# afraid_of_the_dark.net
KiCad netlist of a schematic drawn in EAGLE
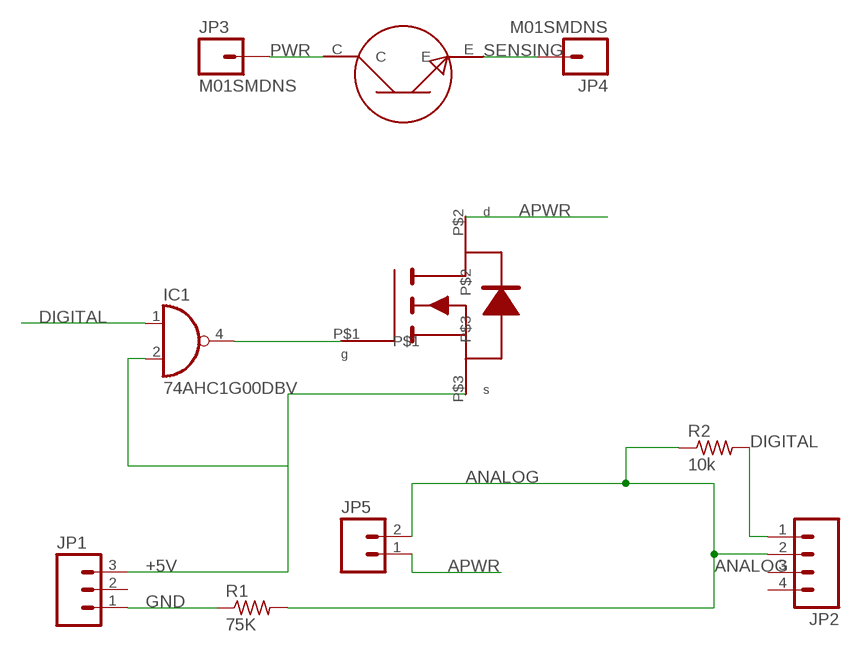
[diagram p0: schematic, sheet 1]

(export (version "E")
  (design (tool "Eeschema 10.0.6"))
  (components
    (comp (ref "IC1")
      (value "74AHC1G00DBV")
      (footprint "eagle-import:SOT23-5")
      (libsource (lib "eagle-import") (part "741G00DBVAHC"))
    )
    (comp (ref "JP1")
      (value "M03PTH")
      (footprint "eagle-import:1X03")
      (libsource (lib "eagle-import") (part "M03PTH"))
    )
    (comp (ref "JP2")
      (value "M04PTH")
      (footprint "eagle-import:1X04")
      (libsource (lib "eagle-import") (part "M04PTH"))
    )
    (comp (ref "JP3")
      (value "M01SMDNS")
      (footprint "eagle-import:1X01NS")
      (libsource (lib "eagle-import") (part "M01SMDNS"))
    )
    (comp (ref "JP4")
      (value "M01SMDNS")
      (footprint "eagle-import:1X01NS")
      (libsource (lib "eagle-import") (part "M01SMDNS"))
    )
    (comp (ref "JP5")
      (value "M023.5MM")
      (footprint "eagle-import:SCREWTERMINAL-3.5MM-2")
      (libsource (lib "eagle-import") (part "M023.5MM"))
    )
    (comp (ref "R1")
      (value "75K")
      (footprint "eagle-import:R0805")
      (libsource (lib "eagle-import") (part "R-US_R0805"))
    )
    (comp (ref "R2")
      (value "10k")
      (footprint "eagle-import:R0805")
      (libsource (lib "eagle-import") (part "R-US_R0805"))
    )
    (comp (ref "U1")
      (value "AMBIENT_LIGHT_SENSOR")
      (footprint "eagle-import:AMBIENT_LIGHT_SENSOR")
      (libsource (lib "eagle-import") (part "AMBIENT_LIGHT_SENSOR"))
    )
    (comp (ref "U3")
      (value "SI2302DS_MOSFET")
      (footprint "eagle-import:SI2302DS_MOSFET")
      (libsource (lib "eagle-import") (part "SI2302DS_MOSFET"))
    )
  )
  (nets
    (net (code "1") (name "/+5V") (class "Default")
      (node (ref "IC1") (pin "2") (pinfunction "I1_2") (pintype "input"))
      (node (ref "JP1") (pin "3") (pinfunction "3_3") (pintype "passive"))
      (node (ref "U3") (pin "P$3") (pinfunction "P$3_P$3") (pintype "bidirectional"))
    )
    (net (code "2") (name "/ANALOG") (class "Default")
      (node (ref "JP2") (pin "2") (pinfunction "2_2") (pintype "passive"))
      (node (ref "JP5") (pin "2") (pinfunction "2_2") (pintype "passive"))
      (node (ref "R1") (pin "2") (pinfunction "2_2") (pintype "passive"))
      (node (ref "R2") (pin "1") (pinfunction "1_1") (pintype "passive"))
    )
    (net (code "3") (name "/APWR") (class "Default")
      (node (ref "JP5") (pin "1") (pinfunction "1_1") (pintype "passive"))
      (node (ref "U3") (pin "P$2") (pinfunction "P$2_P$2") (pintype "bidirectional"))
    )
    (net (code "4") (name "/DIGITAL") (class "Default")
      (node (ref "IC1") (pin "1") (pinfunction "I0_1") (pintype "input"))
      (node (ref "JP2") (pin "1") (pinfunction "1_1") (pintype "passive"))
      (node (ref "R2") (pin "2") (pinfunction "2_2") (pintype "passive"))
    )
    (net (code "5") (name "/GND") (class "Default")
      (node (ref "JP1") (pin "1") (pinfunction "1_1") (pintype "passive"))
      (node (ref "R1") (pin "1") (pinfunction "1_1") (pintype "passive"))
    )
    (net (code "6") (name "/PWR") (class "Default")
      (node (ref "JP3") (pin "1") (pinfunction "1_1") (pintype "passive"))
      (node (ref "U1") (pin "C") (pinfunction "C_C") (pintype "bidirectional"))
    )
    (net (code "7") (name "/SENSING") (class "Default")
      (node (ref "JP4") (pin "1") (pinfunction "1_1") (pintype "passive"))
      (node (ref "U1") (pin "E") (pinfunction "E_E") (pintype "bidirectional"))
    )
    (net (code "8") (name "Net-(IC1A-O)") (class "Default")
      (node (ref "IC1") (pin "4") (pinfunction "O_4") (pintype "output"))
      (node (ref "U3") (pin "P$1") (pinfunction "P$1_P$1") (pintype "bidirectional"))
    )
    (net (code "9") (name "unconnected-(JP1-Pad2)") (class "Default")
      (node (ref "JP1") (pin "2") (pinfunction "2_2") (pintype "passive"))
    )
    (net (code "10") (name "unconnected-(JP2-Pad3)") (class "Default")
      (node (ref "JP2") (pin "3") (pinfunction "3_3") (pintype "passive"))
    )
    (net (code "11") (name "unconnected-(JP2-Pad4)") (class "Default")
      (node (ref "JP2") (pin "4") (pinfunction "4_4") (pintype "passive"))
    )
  )
)
